# referencia.net
KiCad netlist of a schematic drawn in EAGLE
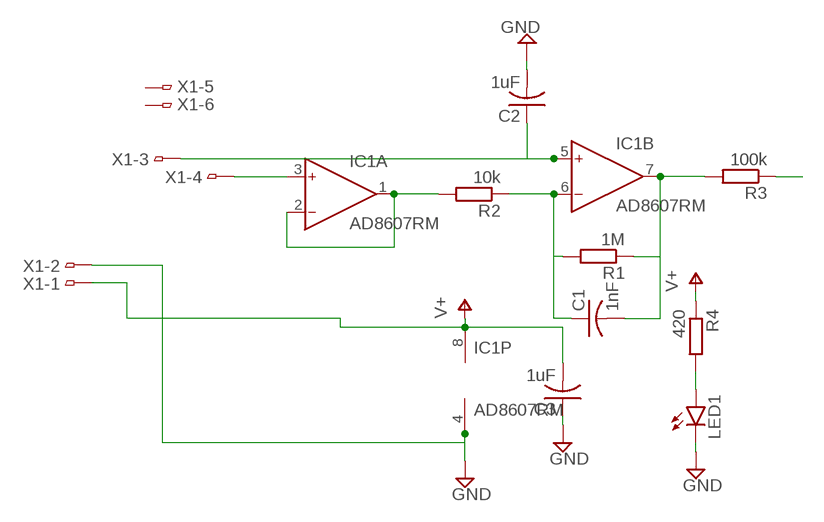
[diagram p0: schematic, sheet 1]

(export (version "E")
  (design (tool "Eeschema 10.0.6"))
  (components
    (comp (ref "C1")
      (value "1nF")
      (footprint "eagle-import:C0603")
      (libsource (lib "eagle-import") (part "C-USC0603"))
    )
    (comp (ref "C2")
      (value "1uF")
      (footprint "eagle-import:C0603")
      (libsource (lib "eagle-import") (part "C-USC0603"))
    )
    (comp (ref "C3")
      (value "1uF")
      (footprint "eagle-import:C0603")
      (libsource (lib "eagle-import") (part "C-USC0603"))
    )
    (comp (ref "IC1")
      (value "AD8607RM")
      (footprint "eagle-import:MSOP08")
      (fields (field (name "MF") "ALTERA CORPORATION") (field (name "MPN") "AD8607ARMZ-REEL"))
      (libsource (lib "eagle-import") (part "AD8607RM"))
    )
    (comp (ref "LED1")
      (value "LEDSML0805")
      (footprint "eagle-import:SML0805")
      (libsource (lib "eagle-import") (part "LEDSML0805"))
    )
    (comp (ref "R1")
      (value "1M")
      (footprint "eagle-import:R0603")
      (libsource (lib "eagle-import") (part "R-EU_R0603"))
    )
    (comp (ref "R2")
      (value "10k")
      (footprint "eagle-import:R0603")
      (libsource (lib "eagle-import") (part "R-EU_R0603"))
    )
    (comp (ref "R3")
      (value "100k")
      (footprint "eagle-import:R0603")
      (libsource (lib "eagle-import") (part "R-EU_R0603"))
    )
    (comp (ref "R4")
      (value "420")
      (footprint "eagle-import:R0603")
      (libsource (lib "eagle-import") (part "R-EU_R0603"))
    )
    (comp (ref "X1")
      (value "FH12-08S-1SH")
      (footprint "eagle-import:FH12-08S-1SH")
      (libsource (lib "eagle-import") (part "FH12-08S-1SH"))
    )
  )
  (nets
    (net (code "1") (name "GND") (class "Default")
      (node (ref "C2") (pin "2") (pinfunction "2_2") (pintype "passive"))
      (node (ref "C3") (pin "1") (pinfunction "1_1") (pintype "passive"))
      (node (ref "IC1") (pin "4") (pinfunction "V-_4") (pintype "power_in"))
      (node (ref "LED1") (pin "C") (pinfunction "C_C") (pintype "passive"))
      (node (ref "X1") (pin "2") (pinfunction "1_2") (pintype "passive"))
    )
    (net (code "2") (name "Net-(IC1A-IN+)") (class "Default")
      (node (ref "IC1") (pin "3") (pinfunction "IN+_3") (pintype "input"))
      (node (ref "X1") (pin "4") (pinfunction "1_4") (pintype "passive"))
    )
    (net (code "3") (name "Net-(IC1A-IN-)") (class "Default")
      (node (ref "IC1") (pin "1") (pinfunction "OUT_1") (pintype "output"))
      (node (ref "IC1") (pin "2") (pinfunction "IN-_2") (pintype "input"))
      (node (ref "R2") (pin "2") (pinfunction "2_2") (pintype "passive"))
    )
    (net (code "4") (name "Net-(IC1B-IN+)") (class "Default")
      (node (ref "C2") (pin "1") (pinfunction "1_1") (pintype "passive"))
      (node (ref "IC1") (pin "5") (pinfunction "IN+_5") (pintype "input"))
      (node (ref "X1") (pin "3") (pinfunction "1_3") (pintype "passive"))
    )
    (net (code "5") (name "Net-(IC1B-IN-)") (class "Default")
      (node (ref "C1") (pin "1") (pinfunction "1_1") (pintype "passive"))
      (node (ref "IC1") (pin "6") (pinfunction "IN-_6") (pintype "input"))
      (node (ref "R1") (pin "2") (pinfunction "2_2") (pintype "passive"))
      (node (ref "R2") (pin "1") (pinfunction "1_1") (pintype "passive"))
    )
    (net (code "6") (name "Net-(IC1B-OUT)") (class "Default")
      (node (ref "C1") (pin "2") (pinfunction "2_2") (pintype "passive"))
      (node (ref "IC1") (pin "7") (pinfunction "OUT_7") (pintype "output"))
      (node (ref "R1") (pin "1") (pinfunction "1_1") (pintype "passive"))
      (node (ref "R3") (pin "2") (pinfunction "2_2") (pintype "passive"))
    )
    (net (code "7") (name "Net-(LED1-PadA)") (class "Default")
      (node (ref "LED1") (pin "A") (pinfunction "A_A") (pintype "passive"))
      (node (ref "R4") (pin "2") (pinfunction "2_2") (pintype "passive"))
    )
    (net (code "8") (name "V+") (class "Default")
      (node (ref "C3") (pin "2") (pinfunction "2_2") (pintype "passive"))
      (node (ref "IC1") (pin "8") (pinfunction "V+_8") (pintype "power_in"))
      (node (ref "R4") (pin "1") (pinfunction "1_1") (pintype "passive"))
      (node (ref "X1") (pin "1") (pinfunction "1_1") (pintype "passive"))
    )
    (net (code "9") (name "unconnected-(R3-Pad1)") (class "Default")
      (node (ref "R3") (pin "1") (pinfunction "1_1") (pintype "passive"))
    )
    (net (code "10") (name "unconnected-(X1E-1-Pad5)") (class "Default")
      (node (ref "X1") (pin "5") (pinfunction "1_5") (pintype "passive"))
    )
    (net (code "11") (name "unconnected-(X1F-1-Pad6)") (class "Default")
      (node (ref "X1") (pin "6") (pinfunction "1_6") (pintype "passive"))
    )
  )
)
